# POWER_CON.net
KiCad netlist of a schematic drawn in Altium Designer
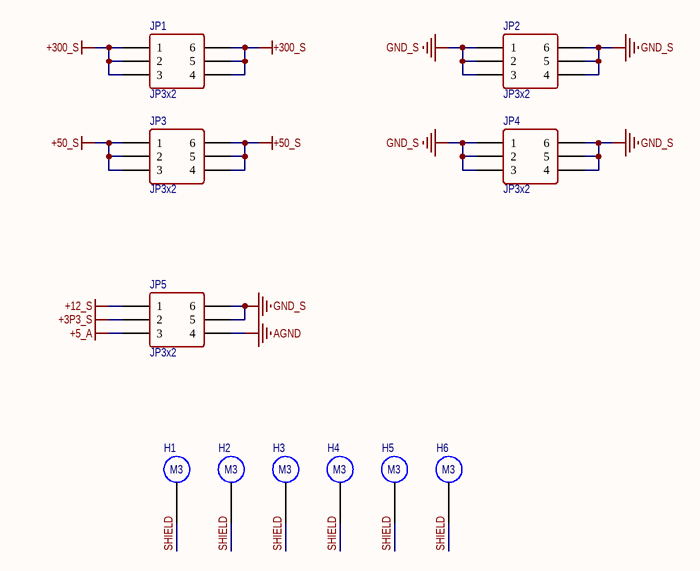
[diagram p0: POWER_CON.SchDoc]

(export (version "E")
  (design (tool "Eeschema 10.0.6"))
  (components
    (comp (ref "H1") (value "M3") (footprint "M3") (libsource (lib "Library") (part "M3")))
    (comp (ref "H2") (value "M3") (footprint "M3") (libsource (lib "Library") (part "M3")))
    (comp (ref "H3") (value "M3") (footprint "M3") (libsource (lib "Library") (part "M3")))
    (comp (ref "H4") (value "M3") (footprint "M3") (libsource (lib "Library") (part "M3")))
    (comp (ref "H5") (value "M3") (footprint "M3") (libsource (lib "Library") (part "M3")))
    (comp (ref "H6") (value "M3") (footprint "M3") (libsource (lib "Library") (part "M3")))
    (comp (ref "JP1")
      (value "JP3x2")
      (footprint "JP3-C2T")
      (description "5-534206-3")
      (fields
        (field (name "MANUFACTURER") "Würth Elektronik eiSos GmbH")
        (field (name "PARTNO") "61300621821")
        (field (name "CREATED BY") "Karrer Zheng")
      )
      (libsource (lib "Library") (part "JP3x2"))
    )
    (comp (ref "JP2")
      (value "JP3x2")
      (footprint "JP3-C2T")
      (description "5-534206-3")
      (fields
        (field (name "MANUFACTURER") "Würth Elektronik eiSos GmbH")
        (field (name "PARTNO") "61300621821")
        (field (name "CREATED BY") "Karrer Zheng")
      )
      (libsource (lib "Library") (part "JP3x2"))
    )
    (comp (ref "JP3")
      (value "JP3x2")
      (footprint "JP3-C2T")
      (description "5-534206-3")
      (fields
        (field (name "MANUFACTURER") "Würth Elektronik eiSos GmbH")
        (field (name "PARTNO") "61300621821")
        (field (name "CREATED BY") "Karrer Zheng")
      )
      (libsource (lib "Library") (part "JP3x2"))
    )
    (comp (ref "JP4")
      (value "JP3x2")
      (footprint "JP3-C2T")
      (description "5-534206-3")
      (fields
        (field (name "MANUFACTURER") "Würth Elektronik eiSos GmbH")
        (field (name "PARTNO") "61300621821")
        (field (name "CREATED BY") "Karrer Zheng")
      )
      (libsource (lib "Library") (part "JP3x2"))
    )
    (comp (ref "JP5")
      (value "JP3x2")
      (footprint "JP3-C2T")
      (description "5-534206-3")
      (fields
        (field (name "MANUFACTURER") "Würth Elektronik eiSos GmbH")
        (field (name "PARTNO") "61300621821")
        (field (name "CREATED BY") "Karrer Zheng")
      )
      (libsource (lib "Library") (part "JP3x2"))
    )
  )
  (nets
    (net (code "1") (name "+3P3_S") (class "Default")
      (node (ref "JP5") (pin "2") (pinfunction "2_2") (pintype "passive"))
    )
    (net (code "2") (name "+5_A") (class "Default")
      (node (ref "JP5") (pin "3") (pinfunction "3_3") (pintype "passive"))
    )
    (net (code "3") (name "+12_S") (class "Default")
      (node (ref "JP5") (pin "1") (pinfunction "1_1") (pintype "passive"))
    )
    (net (code "4") (name "+50_S") (class "Default")
      (node (ref "JP3") (pin "1") (pinfunction "1_1") (pintype "passive"))
      (node (ref "JP3") (pin "2") (pinfunction "2_2") (pintype "passive"))
      (node (ref "JP3") (pin "3") (pinfunction "3_3") (pintype "passive"))
      (node (ref "JP3") (pin "4") (pinfunction "4_4") (pintype "passive"))
      (node (ref "JP3") (pin "5") (pinfunction "5_5") (pintype "passive"))
      (node (ref "JP3") (pin "6") (pinfunction "6_6") (pintype "passive"))
    )
    (net (code "5") (name "+300_S") (class "Default")
      (node (ref "JP1") (pin "1") (pinfunction "1_1") (pintype "passive"))
      (node (ref "JP1") (pin "2") (pinfunction "2_2") (pintype "passive"))
      (node (ref "JP1") (pin "3") (pinfunction "3_3") (pintype "passive"))
      (node (ref "JP1") (pin "4") (pinfunction "4_4") (pintype "passive"))
      (node (ref "JP1") (pin "5") (pinfunction "5_5") (pintype "passive"))
      (node (ref "JP1") (pin "6") (pinfunction "6_6") (pintype "passive"))
    )
    (net (code "6") (name "/SHIELD") (class "Default")
      (node (ref "H1") (pin "1") (pinfunction "76_1") (pintype "passive"))
      (node (ref "H2") (pin "1") (pinfunction "76_1") (pintype "passive"))
      (node (ref "H3") (pin "1") (pinfunction "76_1") (pintype "passive"))
      (node (ref "H4") (pin "1") (pinfunction "76_1") (pintype "passive"))
      (node (ref "H5") (pin "1") (pinfunction "76_1") (pintype "passive"))
      (node (ref "H6") (pin "1") (pinfunction "76_1") (pintype "passive"))
    )
    (net (code "7") (name "AGND") (class "Default")
      (node (ref "JP5") (pin "4") (pinfunction "4_4") (pintype "passive"))
    )
    (net (code "8") (name "GND_S") (class "Default")
      (node (ref "JP2") (pin "1") (pinfunction "1_1") (pintype "passive"))
      (node (ref "JP2") (pin "2") (pinfunction "2_2") (pintype "passive"))
      (node (ref "JP2") (pin "3") (pinfunction "3_3") (pintype "passive"))
      (node (ref "JP2") (pin "4") (pinfunction "4_4") (pintype "passive"))
      (node (ref "JP2") (pin "5") (pinfunction "5_5") (pintype "passive"))
      (node (ref "JP2") (pin "6") (pinfunction "6_6") (pintype "passive"))
      (node (ref "JP4") (pin "1") (pinfunction "1_1") (pintype "passive"))
      (node (ref "JP4") (pin "2") (pinfunction "2_2") (pintype "passive"))
      (node (ref "JP4") (pin "3") (pinfunction "3_3") (pintype "passive"))
      (node (ref "JP4") (pin "4") (pinfunction "4_4") (pintype "passive"))
      (node (ref "JP4") (pin "5") (pinfunction "5_5") (pintype "passive"))
      (node (ref "JP4") (pin "6") (pinfunction "6_6") (pintype "passive"))
      (node (ref "JP5") (pin "5") (pinfunction "5_5") (pintype "passive"))
      (node (ref "JP5") (pin "6") (pinfunction "6_6") (pintype "passive"))
    )
  )
)
